# henryfc.net
KiCad netlist of a schematic drawn in EAGLE
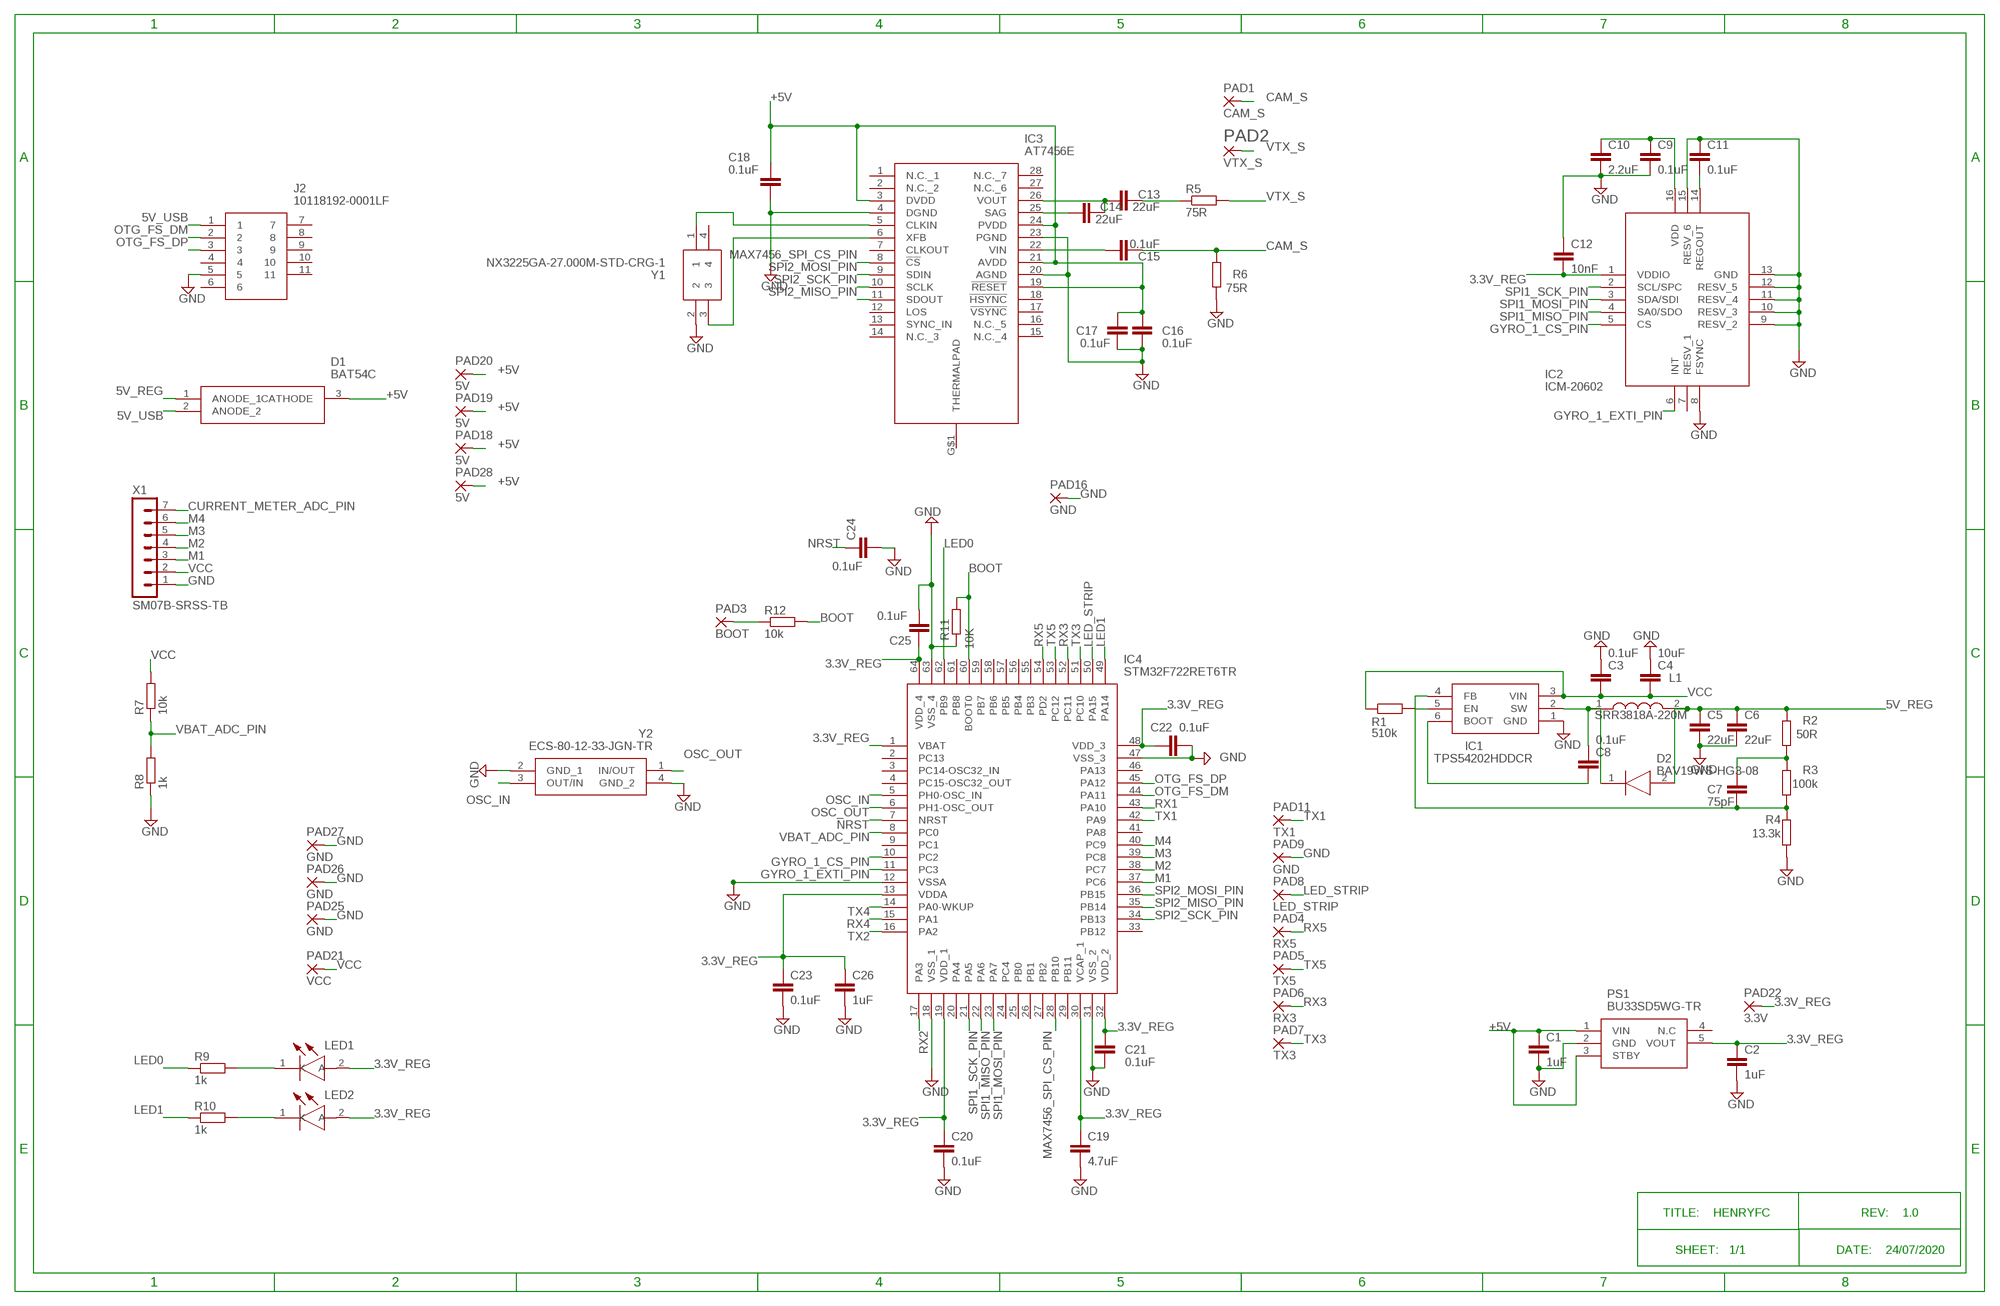
[diagram p0: schematic, sheet 1]

(export (version "E")
  (design (tool "Eeschema 10.0.6"))
  (components
    (comp (ref "C1")
      (value "1uF")
      (footprint "eagle-import:C0603")
      (libsource (lib "eagle-import") (part "C-EUC0603"))
    )
    (comp (ref "C2")
      (value "1uF")
      (footprint "eagle-import:C0603")
      (libsource (lib "eagle-import") (part "C-EUC0603"))
    )
    (comp (ref "C3")
      (value "0.1uF")
      (footprint "eagle-import:C0603")
      (libsource (lib "eagle-import") (part "C-EUC0603"))
    )
    (comp (ref "C4")
      (value "10uF")
      (footprint "eagle-import:C0603")
      (libsource (lib "eagle-import") (part "C-EUC0603"))
    )
    (comp (ref "C5")
      (value "22uF")
      (footprint "eagle-import:C0603")
      (libsource (lib "eagle-import") (part "C-EUC0603"))
    )
    (comp (ref "C6")
      (value "22uF")
      (footprint "eagle-import:C0603")
      (libsource (lib "eagle-import") (part "C-EUC0603"))
    )
    (comp (ref "C7")
      (value "75pF")
      (footprint "eagle-import:C0603")
      (libsource (lib "eagle-import") (part "C-EUC0603"))
    )
    (comp (ref "C8")
      (value "0.1uF")
      (footprint "eagle-import:C0603")
      (libsource (lib "eagle-import") (part "C-EUC0603"))
    )
    (comp (ref "C9")
      (value "0.1uF")
      (footprint "eagle-import:C0603")
      (libsource (lib "eagle-import") (part "C-EUC0603"))
    )
    (comp (ref "C10")
      (value "2.2uF")
      (footprint "eagle-import:C0603")
      (libsource (lib "eagle-import") (part "C-EUC0603"))
    )
    (comp (ref "C11")
      (value "0.1uF")
      (footprint "eagle-import:C0603")
      (libsource (lib "eagle-import") (part "C-EUC0603"))
    )
    (comp (ref "C12")
      (value "10nF")
      (footprint "eagle-import:C0603")
      (libsource (lib "eagle-import") (part "C-EUC0603"))
    )
    (comp (ref "C13")
      (value "22uF")
      (footprint "eagle-import:C0603")
      (libsource (lib "eagle-import") (part "C-EUC0603"))
    )
    (comp (ref "C14")
      (value "22uF")
      (footprint "eagle-import:C0603")
      (libsource (lib "eagle-import") (part "C-EUC0603"))
    )
    (comp (ref "C15")
      (value "0.1uF")
      (footprint "eagle-import:C0603")
      (libsource (lib "eagle-import") (part "C-EUC0603"))
    )
    (comp (ref "C16")
      (value "0.1uF")
      (footprint "eagle-import:C0603")
      (libsource (lib "eagle-import") (part "C-EUC0603"))
    )
    (comp (ref "C17")
      (value "0.1uF")
      (footprint "eagle-import:C0603")
      (libsource (lib "eagle-import") (part "C-EUC0603"))
    )
    (comp (ref "C18")
      (value "0.1uF")
      (footprint "eagle-import:C0603")
      (libsource (lib "eagle-import") (part "C-EUC0603"))
    )
    (comp (ref "C19")
      (value "4.7uF")
      (footprint "eagle-import:C0603")
      (libsource (lib "eagle-import") (part "C-EUC0603"))
    )
    (comp (ref "C20")
      (value "0.1uF")
      (footprint "eagle-import:C0603")
      (libsource (lib "eagle-import") (part "C-EUC0603"))
    )
    (comp (ref "C21")
      (value "0.1uF")
      (footprint "eagle-import:C0603")
      (libsource (lib "eagle-import") (part "C-EUC0603"))
    )
    (comp (ref "C22")
      (value "0.1uF")
      (footprint "eagle-import:C0603")
      (libsource (lib "eagle-import") (part "C-EUC0603"))
    )
    (comp (ref "C23")
      (value "0.1uF")
      (footprint "eagle-import:C0603")
      (libsource (lib "eagle-import") (part "C-EUC0603"))
    )
    (comp (ref "C24")
      (value "0.1uF")
      (footprint "eagle-import:C0603")
      (libsource (lib "eagle-import") (part "C-EUC0603"))
    )
    (comp (ref "C25")
      (value "0.1uF")
      (footprint "eagle-import:C0603")
      (libsource (lib "eagle-import") (part "C-EUC0603"))
    )
    (comp (ref "C26")
      (value "1uF")
      (footprint "eagle-import:C0603")
      (libsource (lib "eagle-import") (part "C-EUC0603"))
    )
    (comp (ref "D1")
      (value "BAT54C")
      (footprint "eagle-import:SOT95P240X120-3N")
      (fields (field (name "MOUSER_PART_NUMBER") "512-BAT54C"))
      (libsource (lib "eagle-import") (part "BAT54C"))
    )
    (comp (ref "D2")
      (value "BAV19WS-HG3-08")
      (footprint "eagle-import:SOD2713X115N")
      (fields (field (name "MOUSER_PART_NUMBER") "78-BAV19WS-HG3-08"))
      (libsource (lib "eagle-import") (part "BAV19WS-HG3-08"))
    )
    (comp (ref "IC1")
      (value "TPS54202HDDCR")
      (footprint "eagle-import:SOT95P280X110-6N")
      (fields (field (name "MOUSER_PART_NUMBER") "595-TPS54202HDDCR"))
      (libsource (lib "eagle-import") (part "TPS54202HDDCR"))
    )
    (comp (ref "IC2")
      (value "ICM-20602")
      (footprint "eagle-import:PULL-BACK-QFN-16")
      (fields (field (name "MOUSER_PART_NUMBER") "410-ICM-20602"))
      (libsource (lib "eagle-import") (part "ICM-20602"))
    )
    (comp (ref "IC3")
      (value "AT7456E")
      (footprint "eagle-import:SOP65P640X120-29N")
      (libsource (lib "eagle-import") (part "AT7456E"))
    )
    (comp (ref "IC4")
      (value "STM32F722RET6TR")
      (footprint "eagle-import:QFP50P1200X1200X160-64N")
      (fields (field (name "MOUSER_PART_NUMBER") "511-STM32F722RET6TR"))
      (libsource (lib "eagle-import") (part "STM32F722RET6TR"))
    )
    (comp (ref "J2")
      (value "10118192-0001LF")
      (footprint "eagle-import:101181920001LF")
      (fields (field (name "MOUSER_PART_NUMBER") "649-10118192-0001LF"))
      (libsource (lib "eagle-import") (part "10118192-0001LF"))
    )
    (comp (ref "L1")
      (value "SRR3818A-220M")
      (footprint "eagle-import:SRR3818A3R3Y")
      (fields (field (name "MOUSER_PART_NUMBER") "652-SRR3818A-220M"))
      (libsource (lib "eagle-import") (part "SRR3818A-220M"))
    )
    (comp (ref "LED1")
      (value "KB_DELPS2.12-QHRI-24-Z555-10-S")
      (footprint "eagle-import:KBDELPS212QHRI24Z55510S")
      (fields
        (field (name "ARROW_PART_NUMBER") "KB DELPS2.12-QHRI-24-Z555-10-S")
        (field (name "MOUSER_PART_NUMBER") "720-KBDELPS212A6350")
      )
      (libsource (lib "eagle-import") (part "KB_DELPS2.12-QHRI-24-Z555-10-S"))
    )
    (comp (ref "LED2")
      (value "KR_DELPS1.22-UHVI-26-H3Q4")
      (footprint "eagle-import:KRDELPS122UHVI26H3Q4")
      (fields
        (field (name "ARROW_PART_NUMBER") "KR DELPS1.22-UHVI-26-H3Q4")
        (field (name "MOUSER_PART_NUMBER") "720-KRDELPS122A5163")
      )
      (libsource (lib "eagle-import") (part "KR_DELPS1.22-UHVI-26-H3Q4"))
    )
    (comp (ref "PAD1")
      (value "CAM_S")
      (footprint "eagle-import:SMD1,27-2,54")
      (libsource (lib "eagle-import") (part "SMD2"))
    )
    (comp (ref "PAD2")
      (value "VTX_S")
      (footprint "eagle-import:SMD1,27-2,54")
      (libsource (lib "eagle-import") (part "SMD2"))
    )
    (comp (ref "PAD3")
      (value "BOOT")
      (footprint "eagle-import:SMD1,27-2,54")
      (libsource (lib "eagle-import") (part "SMD2"))
    )
    (comp (ref "PAD4")
      (value "RX5")
      (footprint "eagle-import:SMD1,27-2,54")
      (libsource (lib "eagle-import") (part "SMD2"))
    )
    (comp (ref "PAD5")
      (value "TX5")
      (footprint "eagle-import:SMD1,27-2,54")
      (libsource (lib "eagle-import") (part "SMD2"))
    )
    (comp (ref "PAD6")
      (value "RX3")
      (footprint "eagle-import:SMD1,27-2,54")
      (libsource (lib "eagle-import") (part "SMD2"))
    )
    (comp (ref "PAD7")
      (value "TX3")
      (footprint "eagle-import:SMD1,27-2,54")
      (libsource (lib "eagle-import") (part "SMD2"))
    )
    (comp (ref "PAD8")
      (value "LED_STRIP")
      (footprint "eagle-import:SMD1,27-2,54")
      (libsource (lib "eagle-import") (part "SMD2"))
    )
    (comp (ref "PAD9")
      (value "GND")
      (footprint "eagle-import:SMD1,27-2,54")
      (libsource (lib "eagle-import") (part "SMD2"))
    )
    (comp (ref "PAD11")
      (value "TX1")
      (footprint "eagle-import:SMD1,27-2,54")
      (libsource (lib "eagle-import") (part "SMD2"))
    )
    (comp (ref "PAD16")
      (value "GND")
      (footprint "eagle-import:SMD1,27-2,54")
      (libsource (lib "eagle-import") (part "SMD2"))
    )
    (comp (ref "PAD18")
      (value "5V")
      (footprint "eagle-import:SMD1,27-2,54")
      (libsource (lib "eagle-import") (part "SMD2"))
    )
    (comp (ref "PAD19")
      (value "5V")
      (footprint "eagle-import:SMD1,27-2,54")
      (libsource (lib "eagle-import") (part "SMD2"))
    )
    (comp (ref "PAD20")
      (value "5V")
      (footprint "eagle-import:SMD1,27-2,54")
      (libsource (lib "eagle-import") (part "SMD2"))
    )
    (comp (ref "PAD21")
      (value "VCC")
      (footprint "eagle-import:SMD1,27-2,54")
      (libsource (lib "eagle-import") (part "SMD2"))
    )
    (comp (ref "PAD22")
      (value "3.3V")
      (footprint "eagle-import:SMD1,27-2,54")
      (libsource (lib "eagle-import") (part "SMD2"))
    )
    (comp (ref "PAD25")
      (value "GND")
      (footprint "eagle-import:SMD1,27-2,54")
      (libsource (lib "eagle-import") (part "SMD2"))
    )
    (comp (ref "PAD26")
      (value "GND")
      (footprint "eagle-import:SMD1,27-2,54")
      (libsource (lib "eagle-import") (part "SMD2"))
    )
    (comp (ref "PAD27")
      (value "GND")
      (footprint "eagle-import:SMD1,27-2,54")
      (libsource (lib "eagle-import") (part "SMD2"))
    )
    (comp (ref "PAD28")
      (value "5V")
      (footprint "eagle-import:SMD1,27-2,54")
      (libsource (lib "eagle-import") (part "SMD2"))
    )
    (comp (ref "PS1")
      (value "BU33SD5WG-TR")
      (footprint "eagle-import:SOT95P280X125-5N")
      (fields (field (name "MOUSER_PART_NUMBER") "755-BU33SD5WG-TR"))
      (libsource (lib "eagle-import") (part "BU33SD5WG-TR"))
    )
    (comp (ref "R1")
      (value "510k")
      (footprint "eagle-import:R0603")
      (libsource (lib "eagle-import") (part "R-EU_R0603"))
    )
    (comp (ref "R2")
      (value "50R")
      (footprint "eagle-import:R0603")
      (libsource (lib "eagle-import") (part "R-EU_R0603"))
    )
    (comp (ref "R3")
      (value "100k")
      (footprint "eagle-import:R0603")
      (libsource (lib "eagle-import") (part "R-EU_R0603"))
    )
    (comp (ref "R4")
      (value "13.3k")
      (footprint "eagle-import:R0603")
      (libsource (lib "eagle-import") (part "R-EU_R0603"))
    )
    (comp (ref "R5")
      (value "75R")
      (footprint "eagle-import:R0603")
      (libsource (lib "eagle-import") (part "R-EU_R0603"))
    )
    (comp (ref "R6")
      (value "75R")
      (footprint "eagle-import:R0603")
      (libsource (lib "eagle-import") (part "R-EU_R0603"))
    )
    (comp (ref "R7")
      (value "10k")
      (footprint "eagle-import:R0603")
      (libsource (lib "eagle-import") (part "R-EU_R0603"))
    )
    (comp (ref "R8")
      (value "1k")
      (footprint "eagle-import:R0603")
      (libsource (lib "eagle-import") (part "R-EU_R0603"))
    )
    (comp (ref "R9")
      (value "1k")
      (footprint "eagle-import:R0603")
      (libsource (lib "eagle-import") (part "R-EU_R0603"))
    )
    (comp (ref "R10")
      (value "1k")
      (footprint "eagle-import:R0603")
      (libsource (lib "eagle-import") (part "R-EU_R0603"))
    )
    (comp (ref "R11")
      (value "10K")
      (footprint "eagle-import:R0603")
      (libsource (lib "eagle-import") (part "R-EU_R0603"))
    )
    (comp (ref "R12")
      (value "10k")
      (footprint "eagle-import:R0603")
      (libsource (lib "eagle-import") (part "R-EU_R0603"))
    )
    (comp (ref "X1")
      (value "SM07B-SRSS-TB")
      (footprint "eagle-import:SM07B-SRSS-TB")
      (libsource (lib "eagle-import") (part "SM07B-SRSS-TB"))
    )
    (comp (ref "Y1")
      (value "NX3225GA-27.000M-STD-CRG-1")
      (footprint "eagle-import:NX3225GA")
      (fields (field (name "MOUSER_PART_NUMBER") "344-NX3225GA27MSTRG1"))
      (libsource (lib "eagle-import") (part "NX3225GA-27.000M-STD-CRG-1"))
    )
    (comp (ref "Y2")
      (value "ECS-80-12-33-JGN-TR")
      (footprint "eagle-import:ECS801233JGNTR")
      (fields (field (name "MOUSER_PART_NUMBER") "520-80-12-33-JGN-TR"))
      (libsource (lib "eagle-import") (part "ECS-80-12-33-JGN-TR"))
    )
  )
  (nets
    (net (code "1") (name "/+5V") (class "Default")
      (node (ref "C1") (pin "1") (pinfunction "1_1") (pintype "passive"))
      (node (ref "C16") (pin "1") (pinfunction "1_1") (pintype "passive"))
      (node (ref "C17") (pin "1") (pinfunction "1_1") (pintype "passive"))
      (node (ref "C18") (pin "2") (pinfunction "2_2") (pintype "passive"))
      (node (ref "D1") (pin "3") (pinfunction "CATHODE_3") (pintype "bidirectional"))
      (node (ref "IC3") (pin "19") (pinfunction "~{RESET}_19") (pintype "bidirectional"))
      (node (ref "IC3") (pin "21") (pinfunction "AVDD_21") (pintype "bidirectional"))
      (node (ref "IC3") (pin "24") (pinfunction "PVDD_24") (pintype "bidirectional"))
      (node (ref "IC3") (pin "3") (pinfunction "DVDD_3") (pintype "bidirectional"))
      (node (ref "PAD18") (pin "1") (pinfunction "P_1") (pintype "passive"))
      (node (ref "PAD19") (pin "1") (pinfunction "P_1") (pintype "passive"))
      (node (ref "PAD20") (pin "1") (pinfunction "P_1") (pintype "passive"))
      (node (ref "PAD28") (pin "1") (pinfunction "P_1") (pintype "passive"))
      (node (ref "PS1") (pin "1") (pinfunction "VIN_1") (pintype "power_in"))
      (node (ref "PS1") (pin "3") (pinfunction "STBY_3") (pintype "input"))
    )
    (net (code "2") (name "/3.3V_REG") (class "Default")
      (node (ref "C12") (pin "2") (pinfunction "2_2") (pintype "passive"))
      (node (ref "C19") (pin "1") (pinfunction "1_1") (pintype "passive"))
      (node (ref "C2") (pin "1") (pinfunction "1_1") (pintype "passive"))
      (node (ref "C20") (pin "1") (pinfunction "1_1") (pintype "passive"))
      (node (ref "C21") (pin "1") (pinfunction "1_1") (pintype "passive"))
      (node (ref "C22") (pin "1") (pinfunction "1_1") (pintype "passive"))
      (node (ref "C23") (pin "1") (pinfunction "1_1") (pintype "passive"))
      (node (ref "C25") (pin "1") (pinfunction "1_1") (pintype "passive"))
      (node (ref "C26") (pin "1") (pinfunction "1_1") (pintype "passive"))
      (node (ref "IC2") (pin "1") (pinfunction "VDDIO_1") (pintype "bidirectional"))
      (node (ref "IC4") (pin "1") (pinfunction "VBAT_1") (pintype "bidirectional"))
      (node (ref "IC4") (pin "13") (pinfunction "VDDA_13") (pintype "bidirectional"))
      (node (ref "IC4") (pin "19") (pinfunction "VDD_1_19") (pintype "bidirectional"))
      (node (ref "IC4") (pin "30") (pinfunction "VCAP_1_30") (pintype "bidirectional"))
      (node (ref "IC4") (pin "32") (pinfunction "VDD_2_32") (pintype "bidirectional"))
      (node (ref "IC4") (pin "48") (pinfunction "VDD_3_48") (pintype "bidirectional"))
      (node (ref "IC4") (pin "64") (pinfunction "VDD_4_64") (pintype "bidirectional"))
      (node (ref "LED1") (pin "2") (pinfunction "A_2") (pintype "bidirectional"))
      (node (ref "LED2") (pin "2") (pinfunction "A_2") (pintype "bidirectional"))
      (node (ref "PAD22") (pin "1") (pinfunction "P_1") (pintype "passive"))
      (node (ref "PS1") (pin "5") (pinfunction "VOUT_5") (pintype "output"))
    )
    (net (code "3") (name "/5V_REG") (class "Default")
      (node (ref "C5") (pin "1") (pinfunction "1_1") (pintype "passive"))
      (node (ref "C6") (pin "1") (pinfunction "1_1") (pintype "passive"))
      (node (ref "D1") (pin "1") (pinfunction "ANODE_1_1") (pintype "bidirectional"))
      (node (ref "D2") (pin "2") (pinfunction "A_2") (pintype "bidirectional"))
      (node (ref "L1") (pin "2") (pinfunction "2_2") (pintype "bidirectional"))
      (node (ref "R2") (pin "2") (pinfunction "2_2") (pintype "passive"))
    )
    (net (code "4") (name "/5V_USB") (class "Default")
      (node (ref "D1") (pin "2") (pinfunction "ANODE_2_2") (pintype "bidirectional"))
      (node (ref "J2") (pin "1") (pinfunction "1_1") (pintype "bidirectional"))
    )
    (net (code "5") (name "/BOOT") (class "Default")
      (node (ref "IC4") (pin "60") (pinfunction "BOOT0_60") (pintype "bidirectional"))
      (node (ref "R11") (pin "2") (pinfunction "2_2") (pintype "passive"))
      (node (ref "R12") (pin "2") (pinfunction "2_2") (pintype "passive"))
    )
    (net (code "6") (name "/CAM_S") (class "Default")
      (node (ref "C15") (pin "2") (pinfunction "2_2") (pintype "passive"))
      (node (ref "PAD1") (pin "1") (pinfunction "P_1") (pintype "passive"))
      (node (ref "R6") (pin "2") (pinfunction "2_2") (pintype "passive"))
    )
    (net (code "7") (name "/CURRENT_METER_ADC_PIN") (class "Default")
      (node (ref "X1") (pin "7") (pinfunction "7_7") (pintype "passive"))
    )
    (net (code "8") (name "/GYRO_1_CS_PIN") (class "Default")
      (node (ref "IC2") (pin "5") (pinfunction "CS_5") (pintype "bidirectional"))
      (node (ref "IC4") (pin "10") (pinfunction "PC2_10") (pintype "bidirectional"))
    )
    (net (code "9") (name "/GYRO_1_EXTI_PIN") (class "Default")
      (node (ref "IC2") (pin "6") (pinfunction "INT_6") (pintype "bidirectional"))
      (node (ref "IC4") (pin "11") (pinfunction "PC3_11") (pintype "bidirectional"))
    )
    (net (code "10") (name "/LED0") (class "Default")
      (node (ref "IC4") (pin "62") (pinfunction "PB9_62") (pintype "bidirectional"))
      (node (ref "R9") (pin "1") (pinfunction "1_1") (pintype "passive"))
    )
    (net (code "11") (name "/LED1") (class "Default")
      (node (ref "IC4") (pin "49") (pinfunction "PA14_49") (pintype "bidirectional"))
      (node (ref "R10") (pin "1") (pinfunction "1_1") (pintype "passive"))
    )
    (net (code "12") (name "/LED_STRIP") (class "Default")
      (node (ref "IC4") (pin "50") (pinfunction "PA15_50") (pintype "bidirectional"))
      (node (ref "PAD8") (pin "1") (pinfunction "P_1") (pintype "passive"))
    )
    (net (code "13") (name "/M1") (class "Default")
      (node (ref "IC4") (pin "37") (pinfunction "PC6_37") (pintype "bidirectional"))
      (node (ref "X1") (pin "3") (pinfunction "3_3") (pintype "passive"))
    )
    (net (code "14") (name "/M2") (class "Default")
      (node (ref "IC4") (pin "38") (pinfunction "PC7_38") (pintype "bidirectional"))
      (node (ref "X1") (pin "4") (pinfunction "4_4") (pintype "passive"))
    )
    (net (code "15") (name "/M3") (class "Default")
      (node (ref "IC4") (pin "39") (pinfunction "PC8_39") (pintype "bidirectional"))
      (node (ref "X1") (pin "5") (pinfunction "5_5") (pintype "passive"))
    )
    (net (code "16") (name "/M4") (class "Default")
      (node (ref "IC4") (pin "40") (pinfunction "PC9_40") (pintype "bidirectional"))
      (node (ref "X1") (pin "6") (pinfunction "6_6") (pintype "passive"))
    )
    (net (code "17") (name "/MAX7456_SPI_CS_PIN") (class "Default")
      (node (ref "IC3") (pin "8") (pinfunction "~{CS}_8") (pintype "bidirectional"))
      (node (ref "IC4") (pin "28") (pinfunction "PB10_28") (pintype "bidirectional"))
    )
    (net (code "18") (name "/NRST") (class "Default")
      (node (ref "C24") (pin "1") (pinfunction "1_1") (pintype "passive"))
      (node (ref "IC4") (pin "7") (pinfunction "NRST_7") (pintype "bidirectional"))
    )
    (net (code "19") (name "/OSC_IN") (class "Default")
      (node (ref "IC4") (pin "5") (pinfunction "PH0-OSC_IN_5") (pintype "bidirectional"))
      (node (ref "Y2") (pin "3") (pinfunction "OUT/IN_3") (pintype "bidirectional"))
    )
    (net (code "20") (name "/OSC_OUT") (class "Default")
      (node (ref "IC4") (pin "6") (pinfunction "PH1-OSC_OUT_6") (pintype "bidirectional"))
      (node (ref "Y2") (pin "1") (pinfunction "IN/OUT_1") (pintype "bidirectional"))
    )
    (net (code "21") (name "/OTG_FS_DM") (class "Default")
      (node (ref "IC4") (pin "44") (pinfunction "PA11_44") (pintype "bidirectional"))
      (node (ref "J2") (pin "2") (pinfunction "2_2") (pintype "bidirectional"))
    )
    (net (code "22") (name "/OTG_FS_DP") (class "Default")
      (node (ref "IC4") (pin "45") (pinfunction "PA12_45") (pintype "bidirectional"))
      (node (ref "J2") (pin "3") (pinfunction "3_3") (pintype "bidirectional"))
    )
    (net (code "23") (name "/RX1") (class "Default")
      (node (ref "IC4") (pin "43") (pinfunction "PA10_43") (pintype "bidirectional"))
    )
    (net (code "24") (name "/RX2") (class "Default")
      (node (ref "IC4") (pin "17") (pinfunction "PA3_17") (pintype "bidirectional"))
    )
    (net (code "25") (name "/RX3") (class "Default")
      (node (ref "IC4") (pin "52") (pinfunction "PC11_52") (pintype "bidirectional"))
      (node (ref "PAD6") (pin "1") (pinfunction "P_1") (pintype "passive"))
    )
    (net (code "26") (name "/RX4") (class "Default")
      (node (ref "IC4") (pin "15") (pinfunction "PA1_15") (pintype "bidirectional"))
    )
    (net (code "27") (name "/RX5") (class "Default")
      (node (ref "IC4") (pin "54") (pinfunction "PD2_54") (pintype "bidirectional"))
      (node (ref "PAD4") (pin "1") (pinfunction "P_1") (pintype "passive"))
    )
    (net (code "28") (name "/SPI1_MISO_PIN") (class "Default")
      (node (ref "IC2") (pin "4") (pinfunction "SA0/SDO_4") (pintype "bidirectional"))
      (node (ref "IC4") (pin "22") (pinfunction "PA6_22") (pintype "bidirectional"))
    )
    (net (code "29") (name "/SPI1_MOSI_PIN") (class "Default")
      (node (ref "IC2") (pin "3") (pinfunction "SDA/SDI_3") (pintype "bidirectional"))
      (node (ref "IC4") (pin "23") (pinfunction "PA7_23") (pintype "bidirectional"))
    )
    (net (code "30") (name "/SPI1_SCK_PIN") (class "Default")
      (node (ref "IC2") (pin "2") (pinfunction "SCL/SPC_2") (pintype "bidirectional"))
      (node (ref "IC4") (pin "21") (pinfunction "PA5_21") (pintype "bidirectional"))
    )
    (net (code "31") (name "/SPI2_MISO_PIN") (class "Default")
      (node (ref "IC3") (pin "11") (pinfunction "SDOUT_11") (pintype "bidirectional"))
      (node (ref "IC4") (pin "35") (pinfunction "PB14_35") (pintype "bidirectional"))
    )
    (net (code "32") (name "/SPI2_MOSI_PIN") (class "Default")
      (node (ref "IC3") (pin "9") (pinfunction "SDIN_9") (pintype "bidirectional"))
      (node (ref "IC4") (pin "36") (pinfunction "PB15_36") (pintype "bidirectional"))
    )
    (net (code "33") (name "/SPI2_SCK_PIN") (class "Default")
      (node (ref "IC3") (pin "10") (pinfunction "SCLK_10") (pintype "bidirectional"))
      (node (ref "IC4") (pin "34") (pinfunction "PB13_34") (pintype "bidirectional"))
    )
    (net (code "34") (name "/TX1") (class "Default")
      (node (ref "IC4") (pin "42") (pinfunction "PA9_42") (pintype "bidirectional"))
      (node (ref "PAD11") (pin "1") (pinfunction "P_1") (pintype "passive"))
    )
    (net (code "35") (name "/TX2") (class "Default")
      (node (ref "IC4") (pin "16") (pinfunction "PA2_16") (pintype "bidirectional"))
    )
    (net (code "36") (name "/TX3") (class "Default")
      (node (ref "IC4") (pin "51") (pinfunction "PC10_51") (pintype "bidirectional"))
      (node (ref "PAD7") (pin "1") (pinfunction "P_1") (pintype "passive"))
    )
    (net (code "37") (name "/TX4") (class "Default")
      (node (ref "IC4") (pin "14") (pinfunction "PA0-WKUP_14") (pintype "bidirectional"))
    )
    (net (code "38") (name "/TX5") (class "Default")
      (node (ref "IC4") (pin "53") (pinfunction "PC12_53") (pintype "bidirectional"))
      (node (ref "PAD5") (pin "1") (pinfunction "P_1") (pintype "passive"))
    )
    (net (code "39") (name "/VBAT_ADC_PIN") (class "Default")
      (node (ref "IC4") (pin "8") (pinfunction "PC0_8") (pintype "bidirectional"))
      (node (ref "R7") (pin "1") (pinfunction "1_1") (pintype "passive"))
      (node (ref "R8") (pin "2") (pinfunction "2_2") (pintype "passive"))
    )
    (net (code "40") (name "/VCC") (class "Default")
      (node (ref "C3") (pin "2") (pinfunction "2_2") (pintype "passive"))
      (node (ref "C4") (pin "2") (pinfunction "2_2") (pintype "passive"))
      (node (ref "IC1") (pin "3") (pinfunction "VIN_3") (pintype "bidirectional"))
      (node (ref "PAD21") (pin "1") (pinfunction "P_1") (pintype "passive"))
      (node (ref "R1") (pin "1") (pinfunction "1_1") (pintype "passive"))
      (node (ref "R7") (pin "2") (pinfunction "2_2") (pintype "passive"))
      (node (ref "X1") (pin "2") (pinfunction "2_2") (pintype "passive"))
    )
    (net (code "41") (name "/VTX_S") (class "Default")
      (node (ref "PAD2") (pin "1") (pinfunction "P_1") (pintype "passive"))
      (node (ref "R5") (pin "2") (pinfunction "2_2") (pintype "passive"))
    )
    (net (code "42") (name "GND") (class "Default")
      (node (ref "C1") (pin "2") (pinfunction "2_2") (pintype "passive"))
      (node (ref "C10") (pin "2") (pinfunction "2_2") (pintype "passive"))
      (node (ref "C11") (pin "1") (pinfunction "1_1") (pintype "passive"))
      (node (ref "C12") (pin "1") (pinfunction "1_1") (pintype "passive"))
      (node (ref "C16") (pin "2") (pinfunction "2_2") (pintype "passive"))
      (node (ref "C17") (pin "2") (pinfunction "2_2") (pintype "passive"))
      (node (ref "C18") (pin "1") (pinfunction "1_1") (pintype "passive"))
      (node (ref "C19") (pin "2") (pinfunction "2_2") (pintype "passive"))
      (node (ref "C2") (pin "2") (pinfunction "2_2") (pintype "passive"))
      (node (ref "C20") (pin "2") (pinfunction "2_2") (pintype "passive"))
      (node (ref "C21") (pin "2") (pinfunction "2_2") (pintype "passive"))
      (node (ref "C22") (pin "2") (pinfunction "2_2") (pintype "passive"))
      (node (ref "C23") (pin "2") (pinfunction "2_2") (pintype "passive"))
      (node (ref "C24") (pin "2") (pinfunction "2_2") (pintype "passive"))
      (node (ref "C25") (pin "2") (pinfunction "2_2") (pintype "passive"))
      (node (ref "C26") (pin "2") (pinfunction "2_2") (pintype "passive"))
      (node (ref "C3") (pin "1") (pinfunction "1_1") (pintype "passive"))
      (node (ref "C4") (pin "1") (pinfunction "1_1") (pintype "passive"))
      (node (ref "C5") (pin "2") (pinfunction "2_2") (pintype "passive"))
      (node (ref "C6") (pin "2") (pinfunction "2_2") (pintype "passive"))
      (node (ref "C9") (pin "2") (pinfunction "2_2") (pintype "passive"))
      (node (ref "IC1") (pin "1") (pinfunction "GND_1") (pintype "bidirectional"))
      (node (ref "IC2") (pin "10") (pinfunction "RESV_3_10") (pintype "bidirectional"))
      (node (ref "IC2") (pin "11") (pinfunction "RESV_4_11") (pintype "bidirectional"))
      (node (ref "IC2") (pin "12") (pinfunction "RESV_5_12") (pintype "bidirectional"))
      (node (ref "IC2") (pin "13") (pinfunction "GND_13") (pintype "bidirectional"))
      (node (ref "IC2") (pin "15") (pinfunction "RESV_6_15") (pintype "bidirectional"))
      (node (ref "IC2") (pin "8") (pinfunction "FSYNC_8") (pintype "bidirectional"))
      (node (ref "IC2") (pin "9") (pinfunction "RESV_2_9") (pintype "bidirectional"))
      (node (ref "IC3") (pin "20") (pinfunction "AGND_20") (pintype "bidirectional"))
      (node (ref "IC3") (pin "23") (pinfunction "PGND_23") (pintype "bidirectional"))
      (node (ref "IC3") (pin "4") (pinfunction "DGND_4") (pintype "bidirectional"))
      (node (ref "IC4") (pin "12") (pinfunction "VSSA_12") (pintype "bidirectional"))
      (node (ref "IC4") (pin "18") (pinfunction "VSS_1_18") (pintype "bidirectional"))
      (node (ref "IC4") (pin "31") (pinfunction "VSS_2_31") (pintype "bidirectional"))
      (node (ref "IC4") (pin "47") (pinfunction "VSS_3_47") (pintype "bidirectional"))
      (node (ref "IC4") (pin "63") (pinfunction "VSS_4_63") (pintype "bidirectional"))
      (node (ref "J2") (pin "5") (pinfunction "5_5") (pintype "bidirectional"))
      (node (ref "PAD16") (pin "1") (pinfunction "P_1") (pintype "passive"))
      (node (ref "PAD25") (pin "1") (pinfunction "P_1") (pintype "passive"))
      (node (ref "PAD26") (pin "1") (pinfunction "P_1") (pintype "passive"))
      (node (ref "PAD27") (pin "1") (pinfunction "P_1") (pintype "passive"))
      (node (ref "PAD9") (pin "1") (pinfunction "P_1") (pintype "passive"))
      (node (ref "PS1") (pin "2") (pinfunction "GND_2") (pintype "power_in"))
      (node (ref "R11") (pin "1") (pinfunction "1_1") (pintype "passive"))
      (node (ref "R4") (pin "1") (pinfunction "1_1") (pintype "passive"))
      (node (ref "R6") (pin "1") (pinfunction "1_1") (pintype "passive"))
      (node (ref "R8") (pin "1") (pinfunction "1_1") (pintype "passive"))
      (node (ref "X1") (pin "1") (pinfunction "1_1") (pintype "passive"))
      (node (ref "Y1") (pin "2") (pinfunction "2_2") (pintype "bidirectional"))
      (node (ref "Y2") (pin "2") (pinfunction "GND_1_2") (pintype "bidirectional"))
      (node (ref "Y2") (pin "4") (pinfunction "GND_2_4") (pintype "bidirectional"))
    )
    (net (code "43") (name "Net-(C7-Pad1)") (class "Default")
      (node (ref "C7") (pin "1") (pinfunction "1_1") (pintype "passive"))
      (node (ref "R2") (pin "1") (pinfunction "1_1") (pintype "passive"))
      (node (ref "R3") (pin "2") (pinfunction "2_2") (pintype "passive"))
    )
    (net (code "44") (name "Net-(C13-Pad2)") (class "Default")
      (node (ref "C13") (pin "2") (pinfunction "2_2") (pintype "passive"))
      (node (ref "R5") (pin "1") (pinfunction "1_1") (pintype "passive"))
    )
    (net (code "45") (name "Net-(D2-K)") (class "Default")
      (node (ref "C8") (pin "1") (pinfunction "1_1") (pintype "passive"))
      (node (ref "D2") (pin "1") (pinfunction "K_1") (pintype "bidirectional"))
      (node (ref "IC1") (pin "2") (pinfunction "SW_2") (pintype "bidirectional"))
      (node (ref "L1") (pin "1") (pinfunction "1_1") (pintype "bidirectional"))
    )
    (net (code "46") (name "Net-(IC1-BOOT)") (class "Default")
      (node (ref "C8") (pin "2") (pinfunction "2_2") (pintype "passive"))
      (node (ref "IC1") (pin "6") (pinfunction "BOOT_6") (pintype "bidirectional"))
    )
    (net (code "47") (name "Net-(IC1-EN)") (class "Default")
      (node (ref "IC1") (pin "5") (pinfunction "EN_5") (pintype "bidirectional"))
      (node (ref "R1") (pin "2") (pinfunction "2_2") (pintype "passive"))
    )
    (net (code "48") (name "Net-(IC1-FB)") (class "Default")
      (node (ref "C7") (pin "2") (pinfunction "2_2") (pintype "passive"))
      (node (ref "IC1") (pin "4") (pinfunction "FB_4") (pintype "bidirectional"))
      (node (ref "R3") (pin "1") (pinfunction "1_1") (pintype "passive"))
      (node (ref "R4") (pin "2") (pinfunction "2_2") (pintype "passive"))
    )
    (net (code "49") (name "Net-(IC2-REGOUT)") (class "Default")
      (node (ref "C11") (pin "2") (pinfunction "2_2") (pintype "passive"))
      (node (ref "IC2") (pin "14") (pinfunction "REGOUT_14") (pintype "bidirectional"))
    )
    (net (code "50") (name "Net-(IC2-VDD)") (class "Default")
      (node (ref "C10") (pin "1") (pinfunction "1_1") (pintype "passive"))
      (node (ref "C9") (pin "1") (pinfunction "1_1") (pintype "passive"))
      (node (ref "IC2") (pin "16") (pinfunction "VDD_16") (pintype "bidirectional"))
    )
    (net (code "51") (name "Net-(IC3-CLKIN)") (class "Default")
      (node (ref "IC3") (pin "5") (pinfunction "CLKIN_5") (pintype "bidirectional"))
      (node (ref "Y1") (pin "1") (pinfunction "1_1") (pintype "bidirectional"))
    )
    (net (code "52") (name "Net-(IC3-SAG)") (class "Default")
      (node (ref "C14") (pin "1") (pinfunction "1_1") (pintype "passive"))
      (node (ref "IC3") (pin "25") (pinfunction "SAG_25") (pintype "bidirectional"))
    )
    (net (code "53") (name "Net-(IC3-VIN)") (class "Default")
      (node (ref "C15") (pin "1") (pinfunction "1_1") (pintype "passive"))
      (node (ref "IC3") (pin "22") (pinfunction "VIN_22") (pintype "bidirectional"))
    )
    (net (code "54") (name "Net-(IC3-VOUT)") (class "Default")
      (node (ref "C13") (pin "1") (pinfunction "1_1") (pintype "passive"))
      (node (ref "C14") (pin "2") (pinfunction "2_2") (pintype "passive"))
      (node (ref "IC3") (pin "26") (pinfunction "VOUT_26") (pintype "bidirectional"))
    )
    (net (code "55") (name "Net-(IC3-XFB)") (class "Default")
      (node (ref "IC3") (pin "6") (pinfunction "XFB_6") (pintype "bidirectional"))
      (node (ref "Y1") (pin "3") (pinfunction "3_3") (pintype "bidirectional"))
    )
    (net (code "56") (name "Net-(LED1-K)") (class "Default")
      (node (ref "LED1") (pin "1") (pinfunction "K_1") (pintype "bidirectional"))
      (node (ref "R9") (pin "2") (pinfunction "2_2") (pintype "passive"))
    )
    (net (code "57") (name "Net-(LED2-K)") (class "Default")
      (node (ref "LED2") (pin "1") (pinfunction "K_1") (pintype "bidirectional"))
      (node (ref "R10") (pin "2") (pinfunction "2_2") (pintype "passive"))
    )
    (net (code "58") (name "Net-(PAD3-P)") (class "Default")
      (node (ref "PAD3") (pin "1") (pinfunction "P_1") (pintype "passive"))
      (node (ref "R12") (pin "1") (pinfunction "1_1") (pintype "passive"))
    )
    (net (code "59") (name "unconnected-(IC2-RESV_1-Pad7)") (class "Default")
      (node (ref "IC2") (pin "7") (pinfunction "RESV_1_7") (pintype "bidirectional"))
    )
    (net (code "60") (name "unconnected-(IC3-CLKOUT-Pad7)") (class "Default")
      (node (ref "IC3") (pin "7") (pinfunction "CLKOUT_7") (pintype "bidirectional"))
    )
    (net (code "61") (name "unconnected-(IC3-LOS-Pad12)") (class "Default")
      (node (ref "IC3") (pin "12") (pinfunction "LOS_12") (pintype "bidirectional"))
    )
    (net (code "62") (name "unconnected-(IC3-N.C._1-Pad1)") (class "Default")
      (node (ref "IC3") (pin "1") (pinfunction "N.C._1_1") (pintype "bidirectional"))
    )
    (net (code "63") (name "unconnected-(IC3-N.C._2-Pad2)") (class "Default")
      (node (ref "IC3") (pin "2") (pinfunction "N.C._2_2") (pintype "bidirectional"))
    )
    (net (code "64") (name "unconnected-(IC3-N.C._3-Pad14)") (class "Default")
      (node (ref "IC3") (pin "14") (pinfunction "N.C._3_14") (pintype "bidirectional"))
    )
    (net (code "65") (name "unconnected-(IC3-N.C._4-Pad15)") (class "Default")
      (node (ref "IC3") (pin "15") (pinfunction "N.C._4_15") (pintype "bidirectional"))
    )
    (net (code "66") (name "unconnected-(IC3-N.C._5-Pad16)") (class "Default")
      (node (ref "IC3") (pin "16") (pinfunction "N.C._5_16") (pintype "bidirectional"))
    )
    (net (code "67") (name "unconnected-(IC3-N.C._6-Pad27)") (class "Default")
      (node (ref "IC3") (pin "27") (pinfunction "N.C._6_27") (pintype "bidirectional"))
    )
    (net (code "68") (name "unconnected-(IC3-N.C._7-Pad28)") (class "Default")
      (node (ref "IC3") (pin "28") (pinfunction "N.C._7_28") (pintype "bidirectional"))
    )
    (net (code "69") (name "unconnected-(IC3-SYNC_IN-Pad13)") (class "Default")
      (node (ref "IC3") (pin "13") (pinfunction "SYNC_IN_13") (pintype "bidirectional"))
    )
    (net (code "70") (name "unconnected-(IC3-THERMALPAD-PadG$1)") (class "Default")
      (node (ref "IC3") (pin "G$1") (pinfunction "THERMALPAD_G$1") (pintype "bidirectional"))
    )
    (net (code "71") (name "unconnected-(IC3-~{HSYNC}-Pad18)") (class "Default")
      (node (ref "IC3") (pin "18") (pinfunction "~{HSYNC}_18") (pintype "bidirectional"))
    )
    (net (code "72") (name "unconnected-(IC3-~{VSYNC}-Pad17)") (class "Default")
      (node (ref "IC3") (pin "17") (pinfunction "~{VSYNC}_17") (pintype "bidirectional"))
    )
    (net (code "73") (name "unconnected-(IC4-PA4-Pad20)") (class "Default")
      (node (ref "IC4") (pin "20") (pinfunction "PA4_20") (pintype "bidirectional"))
    )
    (net (code "74") (name "unconnected-(IC4-PA8-Pad41)") (class "Default")
      (node (ref "IC4") (pin "41") (pinfunction "PA8_41") (pintype "bidirectional"))
    )
    (net (code "75") (name "unconnected-(IC4-PA13-Pad46)") (class "Default")
      (node (ref "IC4") (pin "46") (pinfunction "PA13_46") (pintype "bidirectional"))
    )
    (net (code "76") (name "unconnected-(IC4-PB0-Pad25)") (class "Default")
      (node (ref "IC4") (pin "25") (pinfunction "PB0_25") (pintype "bidirectional"))
    )
    (net (code "77") (name "unconnected-(IC4-PB1-Pad26)") (class "Default")
      (node (ref "IC4") (pin "26") (pinfunction "PB1_26") (pintype "bidirectional"))
    )
    (net (code "78") (name "unconnected-(IC4-PB2-Pad27)") (class "Default")
      (node (ref "IC4") (pin "27") (pinfunction "PB2_27") (pintype "bidirectional"))
    )
    (net (code "79") (name "unconnected-(IC4-PB3-Pad55)") (class "Default")
      (node (ref "IC4") (pin "55") (pinfunction "PB3_55") (pintype "bidirectional"))
    )
    (net (code "80") (name "unconnected-(IC4-PB4-Pad56)") (class "Default")
      (node (ref "IC4") (pin "56") (pinfunction "PB4_56") (pintype "bidirectional"))
    )
    (net (code "81") (name "unconnected-(IC4-PB5-Pad57)") (class "Default")
      (node (ref "IC4") (pin "57") (pinfunction "PB5_57") (pintype "bidirectional"))
    )
    (net (code "82") (name "unconnected-(IC4-PB6-Pad58)") (class "Default")
      (node (ref "IC4") (pin "58") (pinfunction "PB6_58") (pintype "bidirectional"))
    )
    (net (code "83") (name "unconnected-(IC4-PB7-Pad59)") (class "Default")
      (node (ref "IC4") (pin "59") (pinfunction "PB7_59") (pintype "bidirectional"))
    )
    (net (code "84") (name "unconnected-(IC4-PB8-Pad61)") (class "Default")
      (node (ref "IC4") (pin "61") (pinfunction "PB8_61") (pintype "bidirectional"))
    )
    (net (code "85") (name "unconnected-(IC4-PB11-Pad29)") (class "Default")
      (node (ref "IC4") (pin "29") (pinfunction "PB11_29") (pintype "bidirectional"))
    )
    (net (code "86") (name "unconnected-(IC4-PB12-Pad33)") (class "Default")
      (node (ref "IC4") (pin "33") (pinfunction "PB12_33") (pintype "bidirectional"))
    )
    (net (code "87") (name "unconnected-(IC4-PC1-Pad9)") (class "Default")
      (node (ref "IC4") (pin "9") (pinfunction "PC1_9") (pintype "bidirectional"))
    )
    (net (code "88") (name "unconnected-(IC4-PC4-Pad24)") (class "Default")
      (node (ref "IC4") (pin "24") (pinfunction "PC4_24") (pintype "bidirectional"))
    )
    (net (code "89") (name "unconnected-(IC4-PC13-Pad2)") (class "Default")
      (node (ref "IC4") (pin "2") (pinfunction "PC13_2") (pintype "bidirectional"))
    )
    (net (code "90") (name "unconnected-(IC4-PC14-OSC32_IN-Pad3)") (class "Default")
      (node (ref "IC4") (pin "3") (pinfunction "PC14-OSC32_IN_3") (pintype "bidirectional"))
    )
    (net (code "91") (name "unconnected-(IC4-PC15-OSC32_OUT-Pad4)") (class "Default")
      (node (ref "IC4") (pin "4") (pinfunction "PC15-OSC32_OUT_4") (pintype "bidirectional"))
    )
    (net (code "92") (name "unconnected-(J2-Pad4)") (class "Default")
      (node (ref "J2") (pin "4") (pinfunction "4_4") (pintype "bidirectional"))
    )
    (net (code "93") (name "unconnected-(J2-Pad6)") (class "Default")
      (node (ref "J2") (pin "6") (pinfunction "6_6") (pintype "bidirectional"))
    )
    (net (code "94") (name "unconnected-(J2-Pad7)") (class "Default")
      (node (ref "J2") (pin "7") (pinfunction "7_7") (pintype "bidirectional"))
    )
    (net (code "95") (name "unconnected-(J2-Pad8)") (class "Default")
      (node (ref "J2") (pin "8") (pinfunction "8_8") (pintype "bidirectional"))
    )
    (net (code "96") (name "unconnected-(J2-Pad9)") (class "Default")
      (node (ref "J2") (pin "9") (pinfunction "9_9") (pintype "bidirectional"))
    )
    (net (code "97") (name "unconnected-(J2-Pad10)") (class "Default")
      (node (ref "J2") (pin "10") (pinfunction "10_10") (pintype "bidirectional"))
    )
    (net (code "98") (name "unconnected-(J2-Pad11)") (class "Default")
      (node (ref "J2") (pin "11") (pinfunction "11_11") (pintype "bidirectional"))
    )
    (net (code "99") (name "unconnected-(PS1-N.C-Pad4)") (class "Default")
      (node (ref "PS1") (pin "4") (pinfunction "N.C_4") (pintype "no_connect"))
    )
    (net (code "100") (name "unconnected-(Y1-Pad4)") (class "Default")
      (node (ref "Y1") (pin "4") (pinfunction "4_4") (pintype "bidirectional"))
    )
  )
)
